# Debugger.net
KiCad netlist of a schematic drawn in Altium Designer
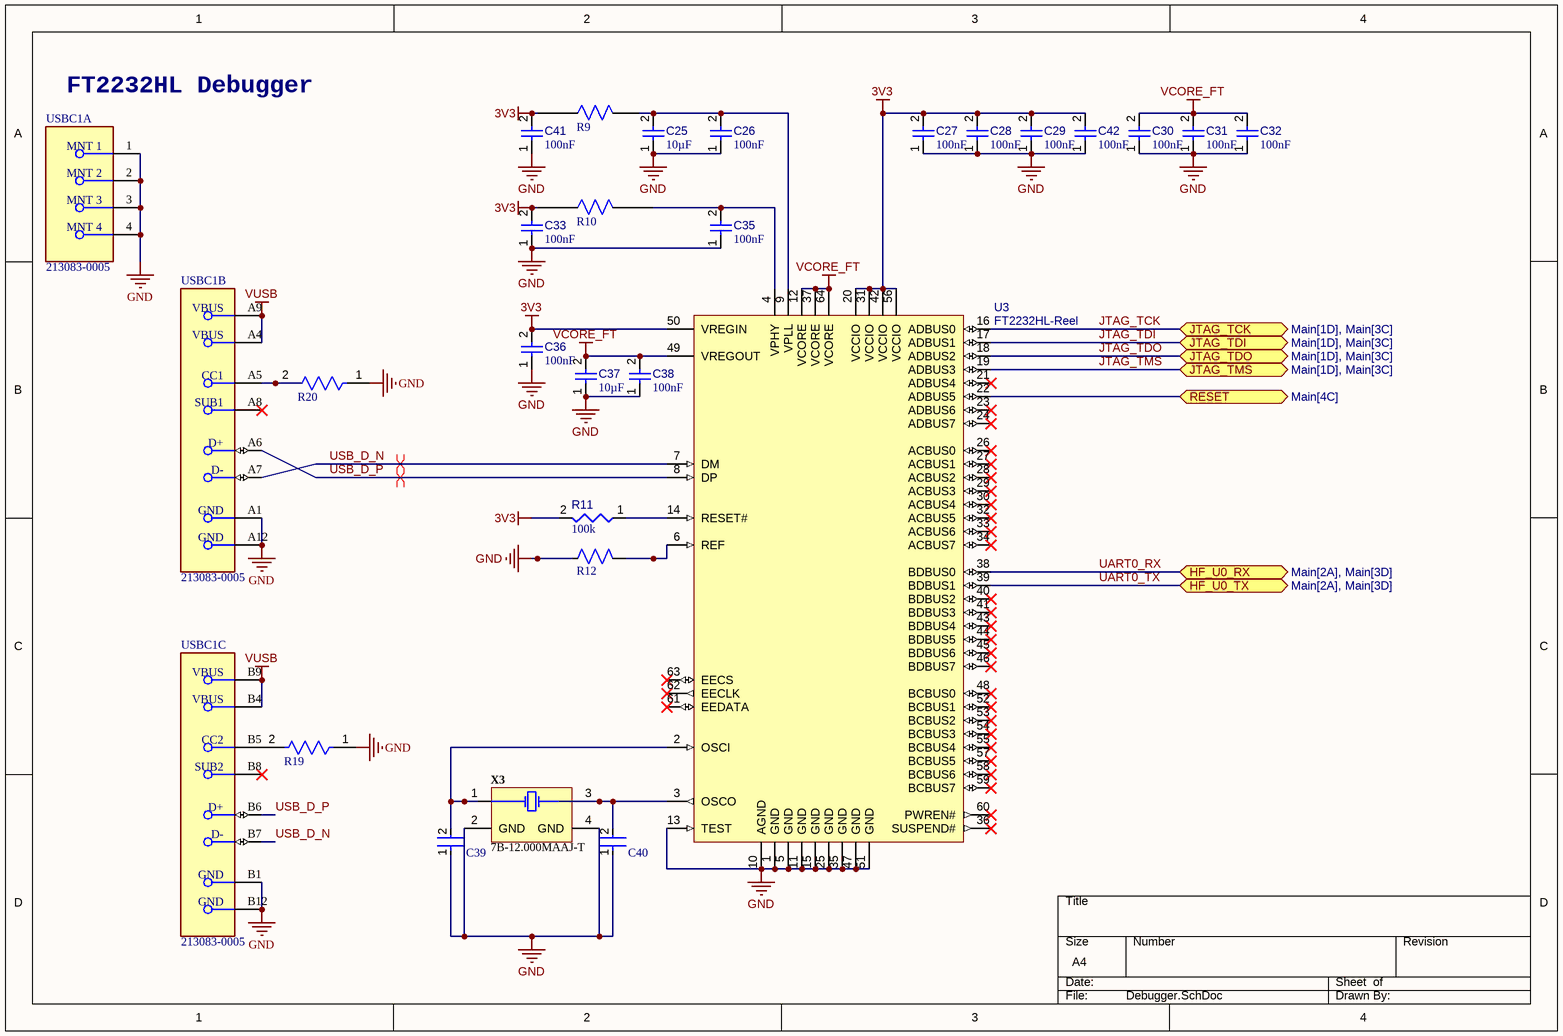
[diagram p0: Debugger.SchDoc]

(export (version "E")
  (design (tool "Eeschema 10.0.6"))
  (components
    (comp (ref "C25")
      (value "10µF")
      (footprint "CAPC0603(1608)100_L")
      (description "Chip Capacitor, 10µF +/-20%, 10V, 0603, Thickness 1 mm")
      (fields (field (name "TOLERANCE") "10%") (field (name "Comment") "Capacitor 10µF +/-20% 10V 0603"))
      (libsource (lib "Rice University") (part "CAP-NP-2"))
    )
    (comp (ref "C26")
      (value "100nF")
      (footprint "CAPC1608X90X40NL10T20")
      (description "Chip Capacitor, 100 nF, +/- 10%, 50 V, 0603 (1608 Metric)")
      (fields (field (name "TOLERANCE") "10%") (field (name "Comment") "Capacitor 100 nF +/-10% 50 V 0603"))
      (libsource (lib "Rice University") (part "CAP-NP-2"))
    )
    (comp (ref "C27")
      (value "100nF")
      (footprint "CAPC1608X90X40NL10T20")
      (description "Chip Capacitor, 100 nF, +/- 10%, 50 V, 0603 (1608 Metric)")
      (fields (field (name "TOLERANCE") "10%") (field (name "Comment") "Capacitor 100 nF +/-10% 50 V 0603"))
      (libsource (lib "Rice University") (part "CAP-NP-2"))
    )
    (comp (ref "C28")
      (value "100nF")
      (footprint "CAPC1608X90X40NL10T20")
      (description "Chip Capacitor, 100 nF, +/- 10%, 50 V, 0603 (1608 Metric)")
      (fields (field (name "TOLERANCE") "10%") (field (name "Comment") "Capacitor 100 nF +/-10% 50 V 0603"))
      (libsource (lib "Rice University") (part "CAP-NP-2"))
    )
    (comp (ref "C29")
      (value "100nF")
      (footprint "CAPC1608X90X40NL10T20")
      (description "Chip Capacitor, 100 nF, +/- 10%, 50 V, 0603 (1608 Metric)")
      (fields (field (name "TOLERANCE") "10%") (field (name "Comment") "Capacitor 100 nF +/-10% 50 V 0603"))
      (libsource (lib "Rice University") (part "CAP-NP-2"))
    )
    (comp (ref "C30")
      (value "100nF")
      (footprint "CAPC1608X90X40NL10T20")
      (description "Chip Capacitor, 100 nF, +/- 10%, 50 V, 0603 (1608 Metric)")
      (fields (field (name "TOLERANCE") "10%") (field (name "Comment") "Capacitor 100 nF +/-10% 50 V 0603"))
      (libsource (lib "Rice University") (part "CAP-NP-2"))
    )
    (comp (ref "C31")
      (value "100nF")
      (footprint "CAPC1608X90X40NL10T20")
      (description "Chip Capacitor, 100 nF, +/- 10%, 50 V, 0603 (1608 Metric)")
      (fields (field (name "TOLERANCE") "10%") (field (name "Comment") "Capacitor 100 nF +/-10% 50 V 0603"))
      (libsource (lib "Rice University") (part "CAP-NP-2"))
    )
    (comp (ref "C32")
      (value "100nF")
      (footprint "CAPC1608X90X40NL10T20")
      (description "Chip Capacitor, 100 nF, +/- 10%, 50 V, 0603 (1608 Metric)")
      (fields (field (name "TOLERANCE") "10%") (field (name "Comment") "Capacitor 100 nF +/-10% 50 V 0603"))
      (libsource (lib "Rice University") (part "CAP-NP-2"))
    )
    (comp (ref "C33")
      (value "100nF")
      (footprint "CAPC1608X90X40NL10T20")
      (description "Chip Capacitor, 100 nF, +/- 10%, 50 V, 0603 (1608 Metric)")
      (fields (field (name "TOLERANCE") "10%") (field (name "Comment") "Capacitor 100 nF +/-10% 50 V 0603"))
      (libsource (lib "Rice University") (part "CAP-NP-2"))
    )
    (comp (ref "C35")
      (value "100nF")
      (footprint "CAPC1608X90X40NL10T20")
      (description "Chip Capacitor, 100 nF, +/- 10%, 50 V, 0603 (1608 Metric)")
      (fields (field (name "TOLERANCE") "10%") (field (name "Comment") "Capacitor 100 nF +/-10% 50 V 0603"))
      (libsource (lib "Rice University") (part "CAP-NP-2"))
    )
    (comp (ref "C36")
      (value "100nF")
      (footprint "CAPC1608X90X40NL10T20")
      (description "Chip Capacitor, 100 nF, +/- 10%, 50 V, 0603 (1608 Metric)")
      (fields (field (name "TOLERANCE") "10%") (field (name "Comment") "Capacitor 100 nF +/-10% 50 V 0603"))
      (libsource (lib "Rice University") (part "CAP-NP-2"))
    )
    (comp (ref "C37")
      (value "10µF")
      (footprint "CAPC0603(1608)100_L")
      (description "Chip Capacitor, 10µF +/-20%, 10V, 0603, Thickness 1 mm")
      (fields (field (name "TOLERANCE") "10%") (field (name "Comment") "Capacitor 10µF +/-20% 10V 0603"))
      (libsource (lib "Rice University") (part "CAP-NP-2"))
    )
    (comp (ref "C38")
      (value "100nF")
      (footprint "CAPC1608X90X40NL10T20")
      (description "Chip Capacitor, 100 nF, +/- 10%, 50 V, 0603 (1608 Metric)")
      (fields (field (name "TOLERANCE") "10%") (field (name "Comment") "Capacitor 100 nF +/-10% 50 V 0603"))
      (libsource (lib "Rice University") (part "CAP-NP-2"))
    )
    (comp (ref "C39")
      (value "06035A220JAT2A")
      (footprint "FP-0603-L_1_6_0_15-W_0_81-IPC_C")
      (description "0603 22 pF 50V ±5% Tolerance C0G/NP0 Surface Mount Multilayer Ceramic Capacitor")
      (libsource (lib "Rice University") (part "02cd4be3c70576c341d710602a673aa"))
    )
    (comp (ref "C40")
      (value "06035A220JAT2A")
      (footprint "FP-0603-L_1_6_0_15-W_0_81-IPC_C")
      (description "0603 22 pF 50V ±5% Tolerance C0G/NP0 Surface Mount Multilayer Ceramic Capacitor")
      (libsource (lib "Rice University") (part "02cd4be3c70576c341d710602a673aa"))
    )
    (comp (ref "C41")
      (value "100nF")
      (footprint "CAPC1608X90X40NL10T20")
      (description "Chip Capacitor, 100 nF, +/- 10%, 50 V, 0603 (1608 Metric)")
      (fields (field (name "TOLERANCE") "10%") (field (name "Comment") "Capacitor 100 nF +/-10% 50 V 0603"))
      (libsource (lib "Rice University") (part "CAP-NP-2"))
    )
    (comp (ref "C42")
      (value "100nF")
      (footprint "CAPC1608X90X40NL10T20")
      (description "Chip Capacitor, 100 nF, +/- 10%, 50 V, 0603 (1608 Metric)")
      (fields (field (name "TOLERANCE") "10%") (field (name "Comment") "Capacitor 100 nF +/-10% 50 V 0603"))
      (libsource (lib "Rice University") (part "CAP-NP-2"))
    )
    (comp (ref "R9")
      (value "PFC-W0603R-02-5R00-F")
      (footprint "PFC-W0603R-02-5R00-F-Footprint-1")
      (description "5 Ohm 1% 50PPM 1/10W")
      (libsource (lib "Rice University") (part "PFC-W0603R-02-5R00-F-Symbol-1"))
    )
    (comp (ref "R10")
      (value "PFC-W0603R-02-5R00-F")
      (footprint "PFC-W0603R-02-5R00-F-Footprint-1")
      (description "5 Ohm 1% 50PPM 1/10W")
      (libsource (lib "Rice University") (part "PFC-W0603R-02-5R00-F-Symbol-1"))
    )
    (comp (ref "R11")
      (value "100k")
      (footprint "RESC1608X55X25ML10T15")
      (description "Chip Resistor, 100 KOhm, +/- 1%, 0.1 W, -55 to 155 degC, 0603 (1608 Metric)")
      (fields (field (name "TOLERANCE") "1%") (field (name "POWER") "100mW"))
      (libsource (lib "Rice University") (part "RES-2"))
    )
    (comp (ref "R12")
      (value "CRG0603F12K")
      (footprint "CRG0603F12K-Footprint-1")
      (description "Res Thick Film 0603 12K Ohm 1% 0.1W(1/10W) ±100ppm/C Pad SMD T/R")
      (libsource (lib "Rice University") (part "CRG0603F12K-Symbol-1"))
    )
    (comp (ref "R19")
      (value "CRCW06035K10JNEA")
      (footprint "FP-CRCW0603-e3-IPC_C")
      (description "Res Thick Film 0603 5.1K Ohm 5% 1/10W ±200ppm/°C Molded SMD SMD Paper T/R")
      (libsource (lib "Rice University") (part "1029c3af85768c4190bb7ad29bc67b5"))
    )
    (comp (ref "R20")
      (value "CRCW06035K10JNEA")
      (footprint "FP-CRCW0603-e3-IPC_C")
      (description "Res Thick Film 0603 5.1K Ohm 5% 1/10W ±200ppm/°C Molded SMD SMD Paper T/R")
      (libsource (lib "Rice University") (part "1029c3af85768c4190bb7ad29bc67b5"))
    )
    (comp (ref "U3")
      (value "FT2232HL-Reel")
      (footprint "LQFP-64_M")
      (description "Dual High Speed USB To Multipurpose UART/FIFO IC, 64-pin LQFP, Tape and Reel")
      (fields (field (name "MANUFACTURER") "FTDI"))
      (libsource (lib "Altium Content Vault") (part "COM-UART-FT2232H-LQFP64"))
    )
    (comp (ref "USBC1")
      (value "213083-0005")
      (footprint "FP-213083-0005-MFG")
      (description "Connector USB Type C Receptacle 16 Position 0.5mm Surface Mount Right Angle Emboss T/R")
      (libsource (lib "Rice University") (part "c515636584ef6ef42fd0bfe97fc1c59"))
    )
    (comp (ref "X3")
      (value "7B-12.000MAAJ-T")
      (footprint "TXC-7B-4_V")
      (fields (field (name "MANUFACTURER") "TXC") (field (name "TOLERANCE") "30ppm"))
      (libsource (lib "Rice University") (part "XTAL-1-3-4"))
    )
  )
  (nets
    (net (code "1") (name "/JTAG_TCK") (class "Default")
      (node (ref "U3") (pin "16") (pinfunction "ADBUS0_16") (pintype "bidirectional"))
    )
    (net (code "2") (name "/JTAG_TDI") (class "Default")
      (node (ref "U3") (pin "17") (pinfunction "ADBUS1_17") (pintype "bidirectional"))
    )
    (net (code "3") (name "/JTAG_TDO") (class "Default")
      (node (ref "U3") (pin "18") (pinfunction "ADBUS2_18") (pintype "bidirectional"))
    )
    (net (code "4") (name "/JTAG_TMS") (class "Default")
      (node (ref "U3") (pin "19") (pinfunction "ADBUS3_19") (pintype "bidirectional"))
    )
    (net (code "5") (name "/RESET") (class "Default")
      (node (ref "U3") (pin "22") (pinfunction "ADBUS5_22") (pintype "bidirectional"))
    )
    (net (code "6") (name "/UART0_RX") (class "Default")
      (node (ref "U3") (pin "38") (pinfunction "BDBUS0_38") (pintype "bidirectional"))
    )
    (net (code "7") (name "/UART0_TX") (class "Default")
      (node (ref "U3") (pin "39") (pinfunction "BDBUS1_39") (pintype "bidirectional"))
    )
    (net (code "8") (name "/USB_D_N") (class "Default")
      (node (ref "U3") (pin "7") (pinfunction "DM_7") (pintype "input"))
      (node (ref "USBC1") (pin "A7") (pinfunction "D-_A7") (pintype "bidirectional"))
      (node (ref "USBC1") (pin "B7") (pinfunction "D-_B7") (pintype "bidirectional"))
    )
    (net (code "9") (name "/USB_D_P") (class "Default")
      (node (ref "U3") (pin "8") (pinfunction "DP_8") (pintype "input"))
      (node (ref "USBC1") (pin "A6") (pinfunction "D+_A6") (pintype "bidirectional"))
      (node (ref "USBC1") (pin "B6") (pinfunction "D+_B6") (pintype "bidirectional"))
    )
    (net (code "10") (name "3V3") (class "Default")
      (node (ref "C27") (pin "2") (pinfunction "2_2") (pintype "passive"))
      (node (ref "C28") (pin "2") (pinfunction "2_2") (pintype "passive"))
      (node (ref "C29") (pin "2") (pinfunction "2_2") (pintype "passive"))
      (node (ref "C33") (pin "2") (pinfunction "2_2") (pintype "passive"))
      (node (ref "C36") (pin "2") (pinfunction "2_2") (pintype "passive"))
      (node (ref "C41") (pin "2") (pinfunction "2_2") (pintype "passive"))
      (node (ref "C42") (pin "2") (pinfunction "2_2") (pintype "passive"))
      (node (ref "R10") (pin "1") (pinfunction "1_1") (pintype "passive"))
      (node (ref "R11") (pin "2") (pinfunction "2_2") (pintype "passive"))
      (node (ref "R9") (pin "1") (pinfunction "1_1") (pintype "passive"))
      (node (ref "U3") (pin "20") (pinfunction "VCCIO_20") (pintype "power_in"))
      (node (ref "U3") (pin "31") (pinfunction "VCCIO_31") (pintype "power_in"))
      (node (ref "U3") (pin "42") (pinfunction "VCCIO_42") (pintype "power_in"))
      (node (ref "U3") (pin "50") (pinfunction "VREGIN_50") (pintype "power_in"))
      (node (ref "U3") (pin "56") (pinfunction "VCCIO_56") (pintype "power_in"))
    )
    (net (code "11") (name "GND") (class "Default")
      (node (ref "C25") (pin "1") (pinfunction "1_1") (pintype "passive"))
      (node (ref "C26") (pin "1") (pinfunction "1_1") (pintype "passive"))
      (node (ref "C27") (pin "1") (pinfunction "1_1") (pintype "passive"))
      (node (ref "C28") (pin "1") (pinfunction "1_1") (pintype "passive"))
      (node (ref "C29") (pin "1") (pinfunction "1_1") (pintype "passive"))
      (node (ref "C30") (pin "1") (pinfunction "1_1") (pintype "passive"))
      (node (ref "C31") (pin "1") (pinfunction "1_1") (pintype "passive"))
      (node (ref "C32") (pin "1") (pinfunction "1_1") (pintype "passive"))
      (node (ref "C33") (pin "1") (pinfunction "1_1") (pintype "passive"))
      (node (ref "C35") (pin "1") (pinfunction "1_1") (pintype "passive"))
      (node (ref "C36") (pin "1") (pinfunction "1_1") (pintype "passive"))
      (node (ref "C37") (pin "1") (pinfunction "1_1") (pintype "passive"))
      (node (ref "C38") (pin "1") (pinfunction "1_1") (pintype "passive"))
      (node (ref "C39") (pin "1") (pinfunction "1_1") (pintype "passive"))
      (node (ref "C40") (pin "1") (pinfunction "1_1") (pintype "passive"))
      (node (ref "C41") (pin "1") (pinfunction "1_1") (pintype "passive"))
      (node (ref "C42") (pin "1") (pinfunction "1_1") (pintype "passive"))
      (node (ref "R12") (pin "1") (pinfunction "1_1") (pintype "passive"))
      (node (ref "R19") (pin "1") (pinfunction "1_1") (pintype "passive"))
      (node (ref "R20") (pin "1") (pinfunction "1_1") (pintype "passive"))
      (node (ref "U3") (pin "1") (pinfunction "GND_1") (pintype "power_in"))
      (node (ref "U3") (pin "10") (pinfunction "AGND_10") (pintype "power_in"))
      (node (ref "U3") (pin "11") (pinfunction "GND_11") (pintype "power_in"))
      (node (ref "U3") (pin "13") (pinfunction "TEST_13") (pintype "input"))
      (node (ref "U3") (pin "15") (pinfunction "GND_15") (pintype "power_in"))
      (node (ref "U3") (pin "25") (pinfunction "GND_25") (pintype "power_in"))
      (node (ref "U3") (pin "35") (pinfunction "GND_35") (pintype "power_in"))
      (node (ref "U3") (pin "47") (pinfunction "GND_47") (pintype "power_in"))
      (node (ref "U3") (pin "5") (pinfunction "GND_5") (pintype "power_in"))
      (node (ref "U3") (pin "51") (pinfunction "GND_51") (pintype "power_in"))
      (node (ref "USBC1") (pin "1") (pinfunction "MNT_1_1") (pintype "passive"))
      (node (ref "USBC1") (pin "2") (pinfunction "MNT_2_2") (pintype "passive"))
      (node (ref "USBC1") (pin "3") (pinfunction "MNT_3_3") (pintype "passive"))
      (node (ref "USBC1") (pin "4") (pinfunction "MNT_4_4") (pintype "passive"))
      (node (ref "USBC1") (pin "A1") (pinfunction "GND_A1") (pintype "power_in"))
      (node (ref "USBC1") (pin "A12") (pinfunction "GND_A12") (pintype "power_in"))
      (node (ref "USBC1") (pin "B1") (pinfunction "GND_B1") (pintype "power_in"))
      (node (ref "USBC1") (pin "B12") (pinfunction "GND_B12") (pintype "power_in"))
      (node (ref "X3") (pin "2") (pinfunction "GND_2") (pintype "power_in"))
      (node (ref "X3") (pin "4") (pinfunction "GND_4") (pintype "power_in"))
    )
    (net (code "12") (name "Net-(U3-OSCI)") (class "Default")
      (node (ref "C39") (pin "2") (pinfunction "2_2") (pintype "passive"))
      (node (ref "U3") (pin "2") (pinfunction "OSCI_2") (pintype "input"))
      (node (ref "X3") (pin "1") (pinfunction "X1_1") (pintype "passive"))
    )
    (net (code "13") (name "Net-(U3-OSCO)") (class "Default")
      (node (ref "C40") (pin "2") (pinfunction "2_2") (pintype "passive"))
      (node (ref "U3") (pin "3") (pinfunction "OSCO_3") (pintype "output"))
      (node (ref "X3") (pin "3") (pinfunction "X2_3") (pintype "passive"))
    )
    (net (code "14") (name "Net-(U3-REF)") (class "Default")
      (node (ref "R12") (pin "2") (pinfunction "2_2") (pintype "passive"))
      (node (ref "U3") (pin "6") (pinfunction "REF_6") (pintype "input"))
    )
    (net (code "15") (name "Net-(U3-RESET#)") (class "Default")
      (node (ref "R11") (pin "1") (pinfunction "1_1") (pintype "passive"))
      (node (ref "U3") (pin "14") (pinfunction "RESET#_14") (pintype "input"))
    )
    (net (code "16") (name "Net-(U3-VPHY)") (class "Default")
      (node (ref "C35") (pin "2") (pinfunction "2_2") (pintype "passive"))
      (node (ref "R10") (pin "2") (pinfunction "2_2") (pintype "passive"))
      (node (ref "U3") (pin "4") (pinfunction "VPHY_4") (pintype "power_in"))
    )
    (net (code "17") (name "Net-(U3-VPLL)") (class "Default")
      (node (ref "C25") (pin "2") (pinfunction "2_2") (pintype "passive"))
      (node (ref "C26") (pin "2") (pinfunction "2_2") (pintype "passive"))
      (node (ref "R9") (pin "2") (pinfunction "2_2") (pintype "passive"))
      (node (ref "U3") (pin "9") (pinfunction "VPLL_9") (pintype "power_in"))
    )
    (net (code "18") (name "Net-(USBC1B-CC1)") (class "Default")
      (node (ref "R20") (pin "2") (pinfunction "2_2") (pintype "passive"))
      (node (ref "USBC1") (pin "A5") (pinfunction "CC1_A5") (pintype "passive"))
    )
    (net (code "19") (name "Net-(USBC1C-CC2)") (class "Default")
      (node (ref "R19") (pin "2") (pinfunction "2_2") (pintype "passive"))
      (node (ref "USBC1") (pin "B5") (pinfunction "CC2_B5") (pintype "passive"))
    )
    (net (code "20") (name "VCORE_FT") (class "Default")
      (node (ref "C30") (pin "2") (pinfunction "2_2") (pintype "passive"))
      (node (ref "C31") (pin "2") (pinfunction "2_2") (pintype "passive"))
      (node (ref "C32") (pin "2") (pinfunction "2_2") (pintype "passive"))
      (node (ref "C37") (pin "2") (pinfunction "2_2") (pintype "passive"))
      (node (ref "C38") (pin "2") (pinfunction "2_2") (pintype "passive"))
      (node (ref "U3") (pin "12") (pinfunction "VCORE_12") (pintype "power_in"))
      (node (ref "U3") (pin "37") (pinfunction "VCORE_37") (pintype "power_in"))
      (node (ref "U3") (pin "49") (pinfunction "VREGOUT_49") (pintype "power_in"))
      (node (ref "U3") (pin "64") (pinfunction "VCORE_64") (pintype "power_in"))
    )
    (net (code "21") (name "VUSB") (class "Default")
      (node (ref "USBC1") (pin "A4") (pinfunction "VBUS_A4") (pintype "passive"))
      (node (ref "USBC1") (pin "A9") (pinfunction "VBUS_A9") (pintype "passive"))
      (node (ref "USBC1") (pin "B4") (pinfunction "VBUS_B4") (pintype "passive"))
      (node (ref "USBC1") (pin "B9") (pinfunction "VBUS_B9") (pintype "passive"))
    )
    (net (code "22") (name "unconnected-(U3-ACBUS0-Pad26)") (class "Default")
      (node (ref "U3") (pin "26") (pinfunction "ACBUS0_26") (pintype "bidirectional+no_connect"))
    )
    (net (code "23") (name "unconnected-(U3-ACBUS1-Pad27)") (class "Default")
      (node (ref "U3") (pin "27") (pinfunction "ACBUS1_27") (pintype "bidirectional+no_connect"))
    )
    (net (code "24") (name "unconnected-(U3-ACBUS2-Pad28)") (class "Default")
      (node (ref "U3") (pin "28") (pinfunction "ACBUS2_28") (pintype "bidirectional+no_connect"))
    )
    (net (code "25") (name "unconnected-(U3-ACBUS3-Pad29)") (class "Default")
      (node (ref "U3") (pin "29") (pinfunction "ACBUS3_29") (pintype "bidirectional+no_connect"))
    )
    (net (code "26") (name "unconnected-(U3-ACBUS4-Pad30)") (class "Default")
      (node (ref "U3") (pin "30") (pinfunction "ACBUS4_30") (pintype "bidirectional+no_connect"))
    )
    (net (code "27") (name "unconnected-(U3-ACBUS5-Pad32)") (class "Default")
      (node (ref "U3") (pin "32") (pinfunction "ACBUS5_32") (pintype "bidirectional+no_connect"))
    )
    (net (code "28") (name "unconnected-(U3-ACBUS6-Pad33)") (class "Default")
      (node (ref "U3") (pin "33") (pinfunction "ACBUS6_33") (pintype "bidirectional+no_connect"))
    )
    (net (code "29") (name "unconnected-(U3-ACBUS7-Pad34)") (class "Default")
      (node (ref "U3") (pin "34") (pinfunction "ACBUS7_34") (pintype "bidirectional+no_connect"))
    )
    (net (code "30") (name "unconnected-(U3-ADBUS4-Pad21)") (class "Default")
      (node (ref "U3") (pin "21") (pinfunction "ADBUS4_21") (pintype "bidirectional+no_connect"))
    )
    (net (code "31") (name "unconnected-(U3-ADBUS6-Pad23)") (class "Default")
      (node (ref "U3") (pin "23") (pinfunction "ADBUS6_23") (pintype "bidirectional+no_connect"))
    )
    (net (code "32") (name "unconnected-(U3-ADBUS7-Pad24)") (class "Default")
      (node (ref "U3") (pin "24") (pinfunction "ADBUS7_24") (pintype "bidirectional+no_connect"))
    )
    (net (code "33") (name "unconnected-(U3-BCBUS0-Pad48)") (class "Default")
      (node (ref "U3") (pin "48") (pinfunction "BCBUS0_48") (pintype "bidirectional+no_connect"))
    )
    (net (code "34") (name "unconnected-(U3-BCBUS1-Pad52)") (class "Default")
      (node (ref "U3") (pin "52") (pinfunction "BCBUS1_52") (pintype "bidirectional+no_connect"))
    )
    (net (code "35") (name "unconnected-(U3-BCBUS2-Pad53)") (class "Default")
      (node (ref "U3") (pin "53") (pinfunction "BCBUS2_53") (pintype "bidirectional+no_connect"))
    )
    (net (code "36") (name "unconnected-(U3-BCBUS3-Pad54)") (class "Default")
      (node (ref "U3") (pin "54") (pinfunction "BCBUS3_54") (pintype "bidirectional+no_connect"))
    )
    (net (code "37") (name "unconnected-(U3-BCBUS4-Pad55)") (class "Default")
      (node (ref "U3") (pin "55") (pinfunction "BCBUS4_55") (pintype "bidirectional+no_connect"))
    )
    (net (code "38") (name "unconnected-(U3-BCBUS5-Pad57)") (class "Default")
      (node (ref "U3") (pin "57") (pinfunction "BCBUS5_57") (pintype "bidirectional+no_connect"))
    )
    (net (code "39") (name "unconnected-(U3-BCBUS6-Pad58)") (class "Default")
      (node (ref "U3") (pin "58") (pinfunction "BCBUS6_58") (pintype "bidirectional+no_connect"))
    )
    (net (code "40") (name "unconnected-(U3-BCBUS7-Pad59)") (class "Default")
      (node (ref "U3") (pin "59") (pinfunction "BCBUS7_59") (pintype "bidirectional+no_connect"))
    )
    (net (code "41") (name "unconnected-(U3-BDBUS2-Pad40)") (class "Default")
      (node (ref "U3") (pin "40") (pinfunction "BDBUS2_40") (pintype "bidirectional+no_connect"))
    )
    (net (code "42") (name "unconnected-(U3-BDBUS3-Pad41)") (class "Default")
      (node (ref "U3") (pin "41") (pinfunction "BDBUS3_41") (pintype "bidirectional+no_connect"))
    )
    (net (code "43") (name "unconnected-(U3-BDBUS4-Pad43)") (class "Default")
      (node (ref "U3") (pin "43") (pinfunction "BDBUS4_43") (pintype "bidirectional+no_connect"))
    )
    (net (code "44") (name "unconnected-(U3-BDBUS5-Pad44)") (class "Default")
      (node (ref "U3") (pin "44") (pinfunction "BDBUS5_44") (pintype "bidirectional+no_connect"))
    )
    (net (code "45") (name "unconnected-(U3-BDBUS6-Pad45)") (class "Default")
      (node (ref "U3") (pin "45") (pinfunction "BDBUS6_45") (pintype "bidirectional+no_connect"))
    )
    (net (code "46") (name "unconnected-(U3-BDBUS7-Pad46)") (class "Default")
      (node (ref "U3") (pin "46") (pinfunction "BDBUS7_46") (pintype "bidirectional+no_connect"))
    )
    (net (code "47") (name "unconnected-(U3-EECLK-Pad62)") (class "Default")
      (node (ref "U3") (pin "62") (pinfunction "EECLK_62") (pintype "output+no_connect"))
    )
    (net (code "48") (name "unconnected-(U3-EECS-Pad63)") (class "Default")
      (node (ref "U3") (pin "63") (pinfunction "EECS_63") (pintype "bidirectional+no_connect"))
    )
    (net (code "49") (name "unconnected-(U3-EEDATA-Pad61)") (class "Default")
      (node (ref "U3") (pin "61") (pinfunction "EEDATA_61") (pintype "bidirectional+no_connect"))
    )
    (net (code "50") (name "unconnected-(U3-PWREN#-Pad60)") (class "Default")
      (node (ref "U3") (pin "60") (pinfunction "PWREN#_60") (pintype "output+no_connect"))
    )
    (net (code "51") (name "unconnected-(U3-SUSPEND#-Pad36)") (class "Default")
      (node (ref "U3") (pin "36") (pinfunction "SUSPEND#_36") (pintype "output+no_connect"))
    )
    (net (code "52") (name "unconnected-(USBC1B-SUB1-PadA8)") (class "Default")
      (node (ref "USBC1") (pin "A8") (pinfunction "SUB1_A8") (pintype "passive+no_connect"))
    )
    (net (code "53") (name "unconnected-(USBC1C-SUB2-PadB8)") (class "Default")
      (node (ref "USBC1") (pin "B8") (pinfunction "SUB2_B8") (pintype "passive+no_connect"))
    )
  )
)
